# power_supply.net
KiCad netlist of a schematic drawn in Altium Designer
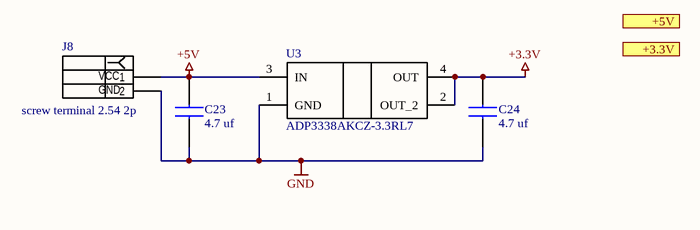
[diagram p0: power_supply.SchDoc]

(export (version "E")
  (design (tool "Eeschema 10.0.6"))
  (components
    (comp (ref "C23")
      (value "4.7 uf")
      (footprint "SamacSys:CAPC1608X90N")
      (description "AVX, SMD MLCC 4.7 uF 10 V dc, 0603")
      (libsource (lib "RobotLib") (part "0603"))
    )
    (comp (ref "C24")
      (value "4.7 uf")
      (footprint "SamacSys:CAPC1608X90N")
      (description "AVX, SMD MLCC 4.7 uF 10 V dc, 0603")
      (libsource (lib "RobotLib") (part "0603"))
    )
    (comp (ref "J8")
      (value "screw terminal 2.54 2p")
      (footprint "1725672-2-2.54")
      (description "Connector")
      (fields
        (field (name "MANUFACTURER_PART_NUMBER") "1725672")
        (field (name "MOUSER PART NUMBER") "651-1725672")
      )
      (libsource (lib "RobotLib") (part "screw terminal 2.54 2p"))
    )
    (comp (ref "U3")
      (value "ADP3338AKCZ-3.3RL7")
      (footprint "SOT230-3")
      (description "Linear Voltage Regulator IC 1 Output 1A SOT-223-3")
      (fields (field (name "MF") "Analog Devices"))
      (libsource (lib "RobotLib") (part "ADP3338AKCZ-3.3RL7"))
    )
  )
  (nets
    (net (code "1") (name "+3.3V") (class "Default")
      (node (ref "C24") (pin "2") (pinfunction "2_2") (pintype "passive"))
      (node (ref "U3") (pin "2") (pinfunction "OUT_2_2") (pintype "passive"))
      (node (ref "U3") (pin "4") (pinfunction "OUT_4") (pintype "passive"))
    )
    (net (code "2") (name "+5V") (class "Default")
      (node (ref "C23") (pin "2") (pinfunction "2_2") (pintype "passive"))
      (node (ref "J8") (pin "1") (pinfunction "1_1") (pintype "passive"))
      (node (ref "U3") (pin "3") (pinfunction "IN_3") (pintype "passive"))
    )
    (net (code "3") (name "GND") (class "Default")
      (node (ref "C23") (pin "1") (pinfunction "1_1") (pintype "passive"))
      (node (ref "C24") (pin "1") (pinfunction "1_1") (pintype "passive"))
      (node (ref "J8") (pin "2") (pinfunction "2_2") (pintype "passive"))
      (node (ref "U3") (pin "1") (pinfunction "GND_1") (pintype "passive"))
    )
  )
)
